# High-Side_Driver.net
KiCad netlist of a schematic drawn in Altium Designer
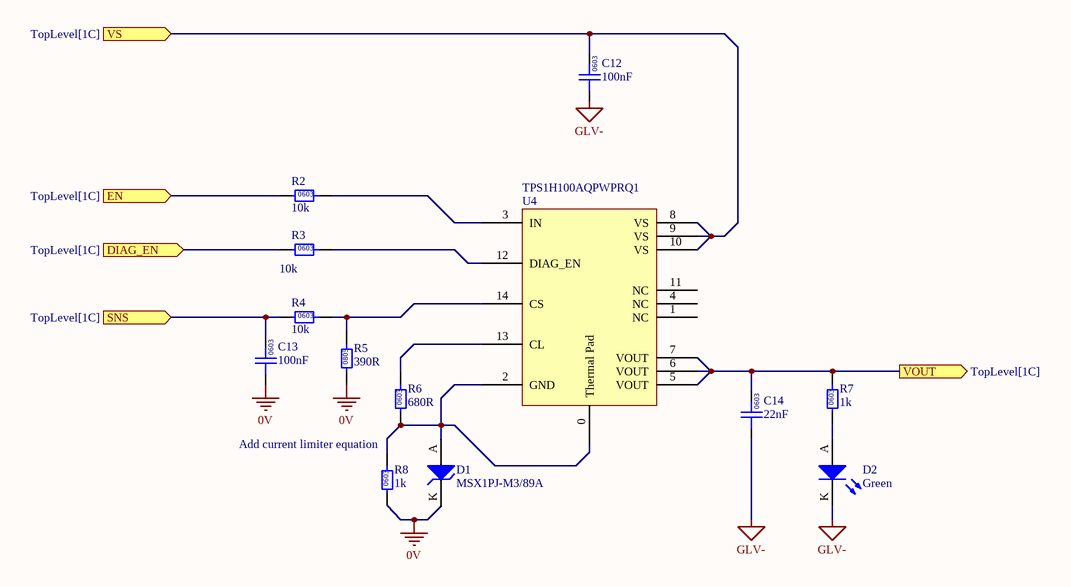
[diagram p0: High-Side Driver.SchDoc]

(export (version "E")
  (design (tool "Eeschema 10.0.6"))
  (components
    (comp (ref "C12")
      (value "100nF")
      (footprint "0603")
      (fields
        (field (name "PART NUMBER") "GCM188L81H104KA57D")
        (field (name "MANUFACTURER") "muRata")
        (field (name "TOLERANCE") "±10%")
      )
      (libsource (lib "ts_standard_library") (part "Capacitor 0603"))
    )
    (comp (ref "C13")
      (value "100nF")
      (footprint "0603")
      (fields
        (field (name "PART NUMBER") "GCM188L81H104KA57D")
        (field (name "MANUFACTURER") "muRata")
        (field (name "TOLERANCE") "±10%")
      )
      (libsource (lib "ts_standard_library") (part "Capacitor 0603"))
    )
    (comp (ref "C14")
      (value "22nF")
      (footprint "0603")
      (fields
        (field (name "PART NUMBER") "GCM188R71H223KA37J")
        (field (name "MANUFACTURER") "Murata Electronics")
        (field (name "TOLERANCE") "±10%")
      )
      (libsource (lib "ts_standard_library") (part "Capacitor 0603"))
    )
    (comp (ref "D1")
      (value "MSX1PJ-M3/89A")
      (footprint "VISHAY DO-219")
      (fields (field (name "MANUFACTURER") "Vishay General Semiconductor - Diodes Division"))
      (libsource (lib "ts_standard_library") (part "Zener Diode"))
    )
    (comp (ref "D2")
      (value "Green")
      (footprint "0805 LED")
      (description "Green LED Indication - Discrete 1.75V 0805 (2012 Metric)")
      (fields (field (name "PART NUMBER") "SML-210FTT86") (field (name "MANUFACTURER") "ROHM Semiconductor"))
      (libsource (lib "ts_standard_library") (part "LED"))
    )
    (comp (ref "R2")
      (value "10k")
      (footprint "0603")
      (fields
        (field (name "PART NUMBER") "RC0603FR-0710KL")
        (field (name "MANUFACTURER") "YAGEO")
        (field (name "TOLERANCE") "0.01")
      )
      (libsource (lib "ts_standard_library") (part "Resistor 0603"))
    )
    (comp (ref "R3")
      (value "10k")
      (footprint "0603")
      (fields
        (field (name "PART NUMBER") "RC0603FR-0710KL")
        (field (name "MANUFACTURER") "YAGEO")
        (field (name "TOLERANCE") "0.01")
      )
      (libsource (lib "ts_standard_library") (part "Resistor 0603"))
    )
    (comp (ref "R4")
      (value "10k")
      (footprint "0603")
      (fields
        (field (name "PART NUMBER") "RC0603FR-0710KL")
        (field (name "MANUFACTURER") "YAGEO")
        (field (name "TOLERANCE") "0.01")
      )
      (libsource (lib "ts_standard_library") (part "Resistor 0603"))
    )
    (comp (ref "R5")
      (value "390R")
      (footprint "0805")
      (fields
        (field (name "PART NUMBER") "RC0805FR07390RL")
        (field (name "MANUFACTURER") "YAGEO")
        (field (name "TOLERANCE") "0.01")
      )
      (libsource (lib "ts_standard_library") (part "Resistor 0805"))
    )
    (comp (ref "R6")
      (value "680R")
      (footprint "0603")
      (fields
        (field (name "PART NUMBER") "RC0603JR-13680RL")
        (field (name "MANUFACTURER") "YAGEO")
        (field (name "TOLERANCE") "0.01")
      )
      (libsource (lib "ts_standard_library") (part "Resistor 0603"))
    )
    (comp (ref "R7")
      (value "1k")
      (footprint "0603")
      (fields
        (field (name "PART NUMBER") "RC0603FR-071KL")
        (field (name "MANUFACTURER") "YAGEO")
        (field (name "TOLERANCE") "0.01")
      )
      (libsource (lib "ts_standard_library") (part "Resistor 0603"))
    )
    (comp (ref "R8")
      (value "1k")
      (footprint "0603")
      (fields
        (field (name "PART NUMBER") "RC0603FR-071KL")
        (field (name "MANUFACTURER") "YAGEO")
        (field (name "TOLERANCE") "0.01")
      )
      (libsource (lib "ts_standard_library") (part "Resistor 0603"))
    )
    (comp (ref "U4")
      (value "TPS1H100AQPWPRQ1")
      (footprint "TI_14_TSSOP")
      (description "IC PWR SWTCH N-CHAN 1:1 14HTSSOP")
      (fields (field (name "MANUFACTURER") "Texas Instruments"))
      (libsource (lib "ts_standard_library") (part "TPS1H100AQPWPRQ1"))
    )
  )
  (nets
    (net (code "1") (name "/DIAG_EN") (class "Default")
      (node (ref "R3") (pin "1") (pinfunction "1_1") (pintype "passive"))
    )
    (net (code "2") (name "/EN") (class "Default")
      (node (ref "R2") (pin "1") (pinfunction "1_1") (pintype "passive"))
    )
    (net (code "3") (name "/SNS") (class "Default")
      (node (ref "C13") (pin "2") (pinfunction "2_2") (pintype "passive"))
      (node (ref "R4") (pin "1") (pinfunction "1_1") (pintype "passive"))
    )
    (net (code "4") (name "/VOUT") (class "Default")
      (node (ref "C14") (pin "2") (pinfunction "2_2") (pintype "passive"))
      (node (ref "R7") (pin "2") (pinfunction "2_2") (pintype "passive"))
      (node (ref "U4") (pin "5") (pinfunction "VOUT_5") (pintype "passive"))
      (node (ref "U4") (pin "6") (pinfunction "VOUT_6") (pintype "passive"))
      (node (ref "U4") (pin "7") (pinfunction "VOUT_7") (pintype "passive"))
    )
    (net (code "5") (name "/VS") (class "Default")
      (node (ref "C12") (pin "2") (pinfunction "2_2") (pintype "passive"))
      (node (ref "U4") (pin "10") (pinfunction "VS_10") (pintype "passive"))
      (node (ref "U4") (pin "8") (pinfunction "VS_8") (pintype "passive"))
      (node (ref "U4") (pin "9") (pinfunction "VS_9") (pintype "passive"))
    )
    (net (code "6") (name "0V") (class "Default")
      (node (ref "C13") (pin "1") (pinfunction "1_1") (pintype "passive"))
      (node (ref "D1") (pin "K") (pinfunction "K_K") (pintype "passive"))
      (node (ref "R5") (pin "1") (pinfunction "1_1") (pintype "passive"))
      (node (ref "R8") (pin "1") (pinfunction "1_1") (pintype "passive"))
    )
    (net (code "7") (name "GLV-") (class "Default")
      (node (ref "C12") (pin "1") (pinfunction "1_1") (pintype "passive"))
      (node (ref "C14") (pin "1") (pinfunction "1_1") (pintype "passive"))
      (node (ref "D2") (pin "K") (pinfunction "K_K") (pintype "passive"))
    )
    (net (code "8") (name "Net-(D2-PadA)") (class "Default")
      (node (ref "D2") (pin "A") (pinfunction "A_A") (pintype "passive"))
      (node (ref "R7") (pin "1") (pinfunction "1_1") (pintype "passive"))
    )
    (net (code "9") (name "Net-(U4-CL)") (class "Default")
      (node (ref "R6") (pin "2") (pinfunction "2_2") (pintype "passive"))
      (node (ref "U4") (pin "13") (pinfunction "CL_13") (pintype "passive"))
    )
    (net (code "10") (name "Net-(U4-CS)") (class "Default")
      (node (ref "R4") (pin "2") (pinfunction "2_2") (pintype "passive"))
      (node (ref "R5") (pin "2") (pinfunction "2_2") (pintype "passive"))
      (node (ref "U4") (pin "14") (pinfunction "CS_14") (pintype "passive"))
    )
    (net (code "11") (name "Net-(U4-DIAG_EN)") (class "Default")
      (node (ref "R3") (pin "2") (pinfunction "2_2") (pintype "passive"))
      (node (ref "U4") (pin "12") (pinfunction "DIAG_EN_12") (pintype "passive"))
    )
    (net (code "12") (name "Net-(U4-GND)") (class "Default")
      (node (ref "D1") (pin "A") (pinfunction "A_A") (pintype "passive"))
      (node (ref "R6") (pin "1") (pinfunction "1_1") (pintype "passive"))
      (node (ref "R8") (pin "2") (pinfunction "2_2") (pintype "passive"))
      (node (ref "U4") (pin "0") (pinfunction "Thermal_Pad_0") (pintype "passive"))
      (node (ref "U4") (pin "2") (pinfunction "GND_2") (pintype "passive"))
    )
    (net (code "13") (name "Net-(U4-IN)") (class "Default")
      (node (ref "R2") (pin "2") (pinfunction "2_2") (pintype "passive"))
      (node (ref "U4") (pin "3") (pinfunction "IN_3") (pintype "passive"))
    )
    (net (code "14") (name "unconnected-(U4-NC-Pad1)") (class "Default")
      (node (ref "U4") (pin "1") (pinfunction "NC_1") (pintype "passive"))
    )
    (net (code "15") (name "unconnected-(U4-NC-Pad4)") (class "Default")
      (node (ref "U4") (pin "4") (pinfunction "NC_4") (pintype "passive"))
    )
    (net (code "16") (name "unconnected-(U4-NC-Pad11)") (class "Default")
      (node (ref "U4") (pin "11") (pinfunction "NC_11") (pintype "passive"))
    )
  )
)
